# port-expander.net
KiCad netlist of a schematic drawn in Altium Designer
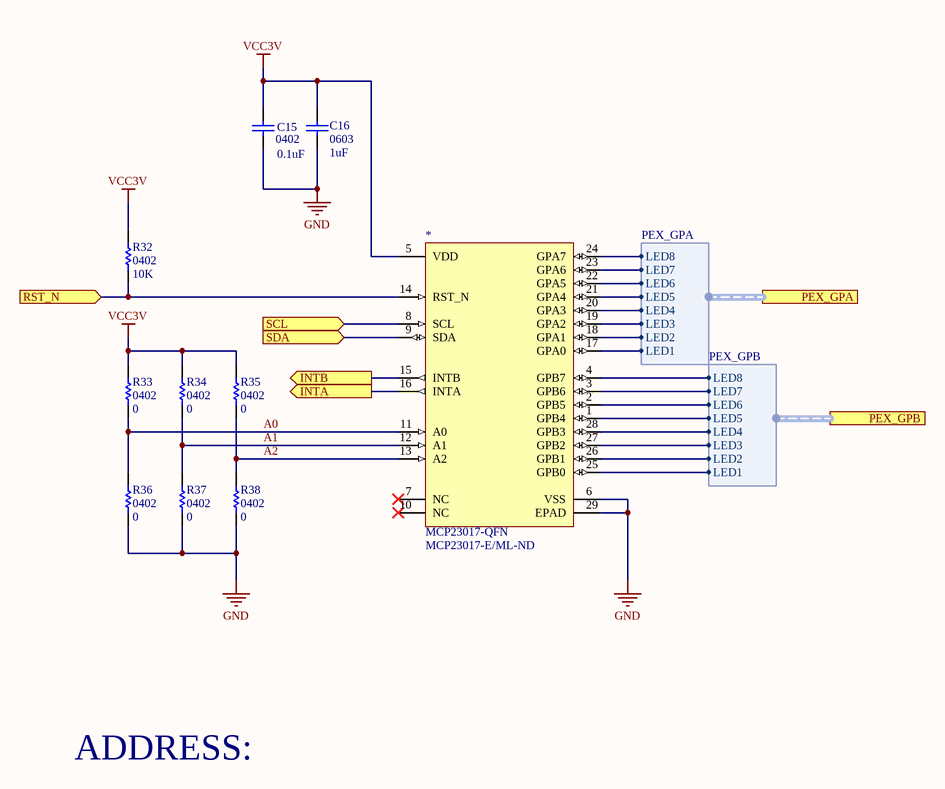
[diagram p0: port-expander.SchDoc]

(export (version "E")
  (design (tool "Eeschema 10.0.6"))
  (components
    (comp (ref "*")
      (value "MCP23017-QFN")
      (footprint "QFN65P600X600X100-29")
      (fields (field (name "SUPPLIER PART NUMBER 1") "MCP23017-E/ML-ND"))
      (libsource (lib "heron-general") (part "MCP23017-QFN"))
    )
    (comp (ref "C15")
      (value "0402")
      (footprint "1608[0603]")
      (description "Capacitor (Semiconductor SIM Model)")
      (fields (field (name "ALTIUM_VALUE") "0.1uF") (field (name "PUBLISHER") "Altium Limited"))
      (libsource (lib "Miscellaneous Devices") (part "Cap Semi"))
    )
    (comp (ref "C16")
      (value "0603")
      (footprint "RAD-0.3")
      (description "Capacitor")
      (fields (field (name "ALTIUM_VALUE") "1uF") (field (name "PUBLISHER") "Altium Limited"))
      (libsource (lib "Miscellaneous Devices") (part "Cap"))
    )
    (comp (ref "R32")
      (value "0402")
      (footprint "AXIAL-0.3")
      (description "Resistor")
      (fields (field (name "ALTIUM_VALUE") "10K") (field (name "PUBLISHER") "Altium Limited"))
      (libsource (lib "Miscellaneous Devices") (part "Res1"))
    )
    (comp (ref "R33")
      (value "0402")
      (footprint "AXIAL-0.3")
      (description "Resistor")
      (fields (field (name "ALTIUM_VALUE") "0") (field (name "PUBLISHER") "Altium Limited"))
      (libsource (lib "Miscellaneous Devices") (part "Res1"))
    )
    (comp (ref "R34")
      (value "0402")
      (footprint "AXIAL-0.3")
      (description "Resistor")
      (fields (field (name "ALTIUM_VALUE") "0") (field (name "PUBLISHER") "Altium Limited"))
      (libsource (lib "Miscellaneous Devices") (part "Res1"))
    )
    (comp (ref "R35")
      (value "0402")
      (footprint "AXIAL-0.3")
      (description "Resistor")
      (fields (field (name "ALTIUM_VALUE") "0") (field (name "PUBLISHER") "Altium Limited"))
      (libsource (lib "Miscellaneous Devices") (part "Res1"))
    )
    (comp (ref "R36")
      (value "0402")
      (footprint "AXIAL-0.3")
      (description "Resistor")
      (fields (field (name "ALTIUM_VALUE") "0") (field (name "PUBLISHER") "Altium Limited"))
      (libsource (lib "Miscellaneous Devices") (part "Res1"))
    )
    (comp (ref "R37")
      (value "0402")
      (footprint "AXIAL-0.3")
      (description "Resistor")
      (fields (field (name "ALTIUM_VALUE") "0") (field (name "PUBLISHER") "Altium Limited"))
      (libsource (lib "Miscellaneous Devices") (part "Res1"))
    )
    (comp (ref "R38")
      (value "0402")
      (footprint "AXIAL-0.3")
      (description "Resistor")
      (fields (field (name "ALTIUM_VALUE") "0") (field (name "PUBLISHER") "Altium Limited"))
      (libsource (lib "Miscellaneous Devices") (part "Res1"))
    )
  )
  (nets
    (net (code "3") (name "/A0") (class "Default")
      (node (ref "*") (pin "11") (pinfunction "A0_11") (pintype "input"))
      (node (ref "R33") (pin "1") (pinfunction "1_1") (pintype "passive"))
      (node (ref "R36") (pin "2") (pinfunction "2_2") (pintype "passive"))
    )
    (net (code "4") (name "/A1") (class "Default")
      (node (ref "*") (pin "12") (pinfunction "A1_12") (pintype "input"))
      (node (ref "R34") (pin "1") (pinfunction "1_1") (pintype "passive"))
      (node (ref "R37") (pin "2") (pinfunction "2_2") (pintype "passive"))
    )
    (net (code "5") (name "/A2") (class "Default")
      (node (ref "*") (pin "13") (pinfunction "A2_13") (pintype "input"))
      (node (ref "R35") (pin "1") (pinfunction "1_1") (pintype "passive"))
      (node (ref "R38") (pin "2") (pinfunction "2_2") (pintype "passive"))
    )
    (net (code "6") (name "/INTA") (class "Default")
      (node (ref "*") (pin "16") (pinfunction "INTA_16") (pintype "output"))
    )
    (net (code "7") (name "/INTB") (class "Default")
      (node (ref "*") (pin "15") (pinfunction "INTB_15") (pintype "output"))
    )
    (net (code "8") (name "/RST_N") (class "Default")
      (node (ref "*") (pin "14") (pinfunction "RST_N_14") (pintype "input"))
      (node (ref "R32") (pin "1") (pinfunction "1_1") (pintype "passive"))
    )
    (net (code "9") (name "/SCL") (class "Default")
      (node (ref "*") (pin "8") (pinfunction "SCL_8") (pintype "input"))
    )
    (net (code "10") (name "/SDA") (class "Default")
      (node (ref "*") (pin "9") (pinfunction "SDA_9") (pintype "bidirectional"))
    )
    (net (code "13") (name "GND") (class "Default")
      (node (ref "*") (pin "29") (pinfunction "EPAD_29") (pintype "power_in"))
      (node (ref "*") (pin "6") (pinfunction "VSS_6") (pintype "power_in"))
      (node (ref "C15") (pin "1") (pinfunction "1_1") (pintype "passive"))
      (node (ref "C16") (pin "1") (pinfunction "1_1") (pintype "passive"))
      (node (ref "R36") (pin "1") (pinfunction "1_1") (pintype "passive"))
      (node (ref "R37") (pin "1") (pinfunction "1_1") (pintype "passive"))
      (node (ref "R38") (pin "1") (pinfunction "1_1") (pintype "passive"))
    )
    (net (code "14") (name "VCC3V") (class "Default")
      (node (ref "*") (pin "5") (pinfunction "VDD_5") (pintype "power_in"))
      (node (ref "C15") (pin "2") (pinfunction "2_2") (pintype "passive"))
      (node (ref "C16") (pin "2") (pinfunction "2_2") (pintype "passive"))
      (node (ref "R32") (pin "2") (pinfunction "2_2") (pintype "passive"))
      (node (ref "R33") (pin "2") (pinfunction "2_2") (pintype "passive"))
      (node (ref "R34") (pin "2") (pinfunction "2_2") (pintype "passive"))
      (node (ref "R35") (pin "2") (pinfunction "2_2") (pintype "passive"))
    )
    (net (code "15") (name "unconnected-(*-GPA0-Pad17)") (class "Default")
      (node (ref "*") (pin "17") (pinfunction "GPA0_17") (pintype "bidirectional"))
    )
    (net (code "16") (name "unconnected-(*-GPA1-Pad18)") (class "Default")
      (node (ref "*") (pin "18") (pinfunction "GPA1_18") (pintype "bidirectional"))
    )
    (net (code "17") (name "unconnected-(*-GPA2-Pad19)") (class "Default")
      (node (ref "*") (pin "19") (pinfunction "GPA2_19") (pintype "bidirectional"))
    )
    (net (code "18") (name "unconnected-(*-GPA3-Pad20)") (class "Default")
      (node (ref "*") (pin "20") (pinfunction "GPA3_20") (pintype "bidirectional"))
    )
    (net (code "19") (name "unconnected-(*-GPA4-Pad21)") (class "Default")
      (node (ref "*") (pin "21") (pinfunction "GPA4_21") (pintype "bidirectional"))
    )
    (net (code "20") (name "unconnected-(*-GPA5-Pad22)") (class "Default")
      (node (ref "*") (pin "22") (pinfunction "GPA5_22") (pintype "bidirectional"))
    )
    (net (code "21") (name "unconnected-(*-GPA6-Pad23)") (class "Default")
      (node (ref "*") (pin "23") (pinfunction "GPA6_23") (pintype "bidirectional"))
    )
    (net (code "22") (name "unconnected-(*-GPA7-Pad24)") (class "Default")
      (node (ref "*") (pin "24") (pinfunction "GPA7_24") (pintype "bidirectional"))
    )
    (net (code "23") (name "unconnected-(*-GPB0-Pad25)") (class "Default")
      (node (ref "*") (pin "25") (pinfunction "GPB0_25") (pintype "bidirectional"))
    )
    (net (code "24") (name "unconnected-(*-GPB1-Pad26)") (class "Default")
      (node (ref "*") (pin "26") (pinfunction "GPB1_26") (pintype "bidirectional"))
    )
    (net (code "25") (name "unconnected-(*-GPB2-Pad27)") (class "Default")
      (node (ref "*") (pin "27") (pinfunction "GPB2_27") (pintype "bidirectional"))
    )
    (net (code "26") (name "unconnected-(*-GPB3-Pad28)") (class "Default")
      (node (ref "*") (pin "28") (pinfunction "GPB3_28") (pintype "bidirectional"))
    )
    (net (code "27") (name "unconnected-(*-GPB4-Pad1)") (class "Default")
      (node (ref "*") (pin "1") (pinfunction "GPB4_1") (pintype "bidirectional"))
    )
    (net (code "28") (name "unconnected-(*-GPB5-Pad2)") (class "Default")
      (node (ref "*") (pin "2") (pinfunction "GPB5_2") (pintype "bidirectional"))
    )
    (net (code "29") (name "unconnected-(*-GPB6-Pad3)") (class "Default")
      (node (ref "*") (pin "3") (pinfunction "GPB6_3") (pintype "bidirectional"))
    )
    (net (code "30") (name "unconnected-(*-GPB7-Pad4)") (class "Default")
      (node (ref "*") (pin "4") (pinfunction "GPB7_4") (pintype "bidirectional"))
    )
    (net (code "31") (name "unconnected-(*-NC-Pad7)") (class "Default")
      (node (ref "*") (pin "7") (pinfunction "NC_7") (pintype "passive+no_connect"))
    )
    (net (code "32") (name "unconnected-(*-NC-Pad10)") (class "Default")
      (node (ref "*") (pin "10") (pinfunction "NC_10") (pintype "passive+no_connect"))
    )
  )
)
